# BlindsControl.net
KiCad netlist of a schematic drawn in EAGLE
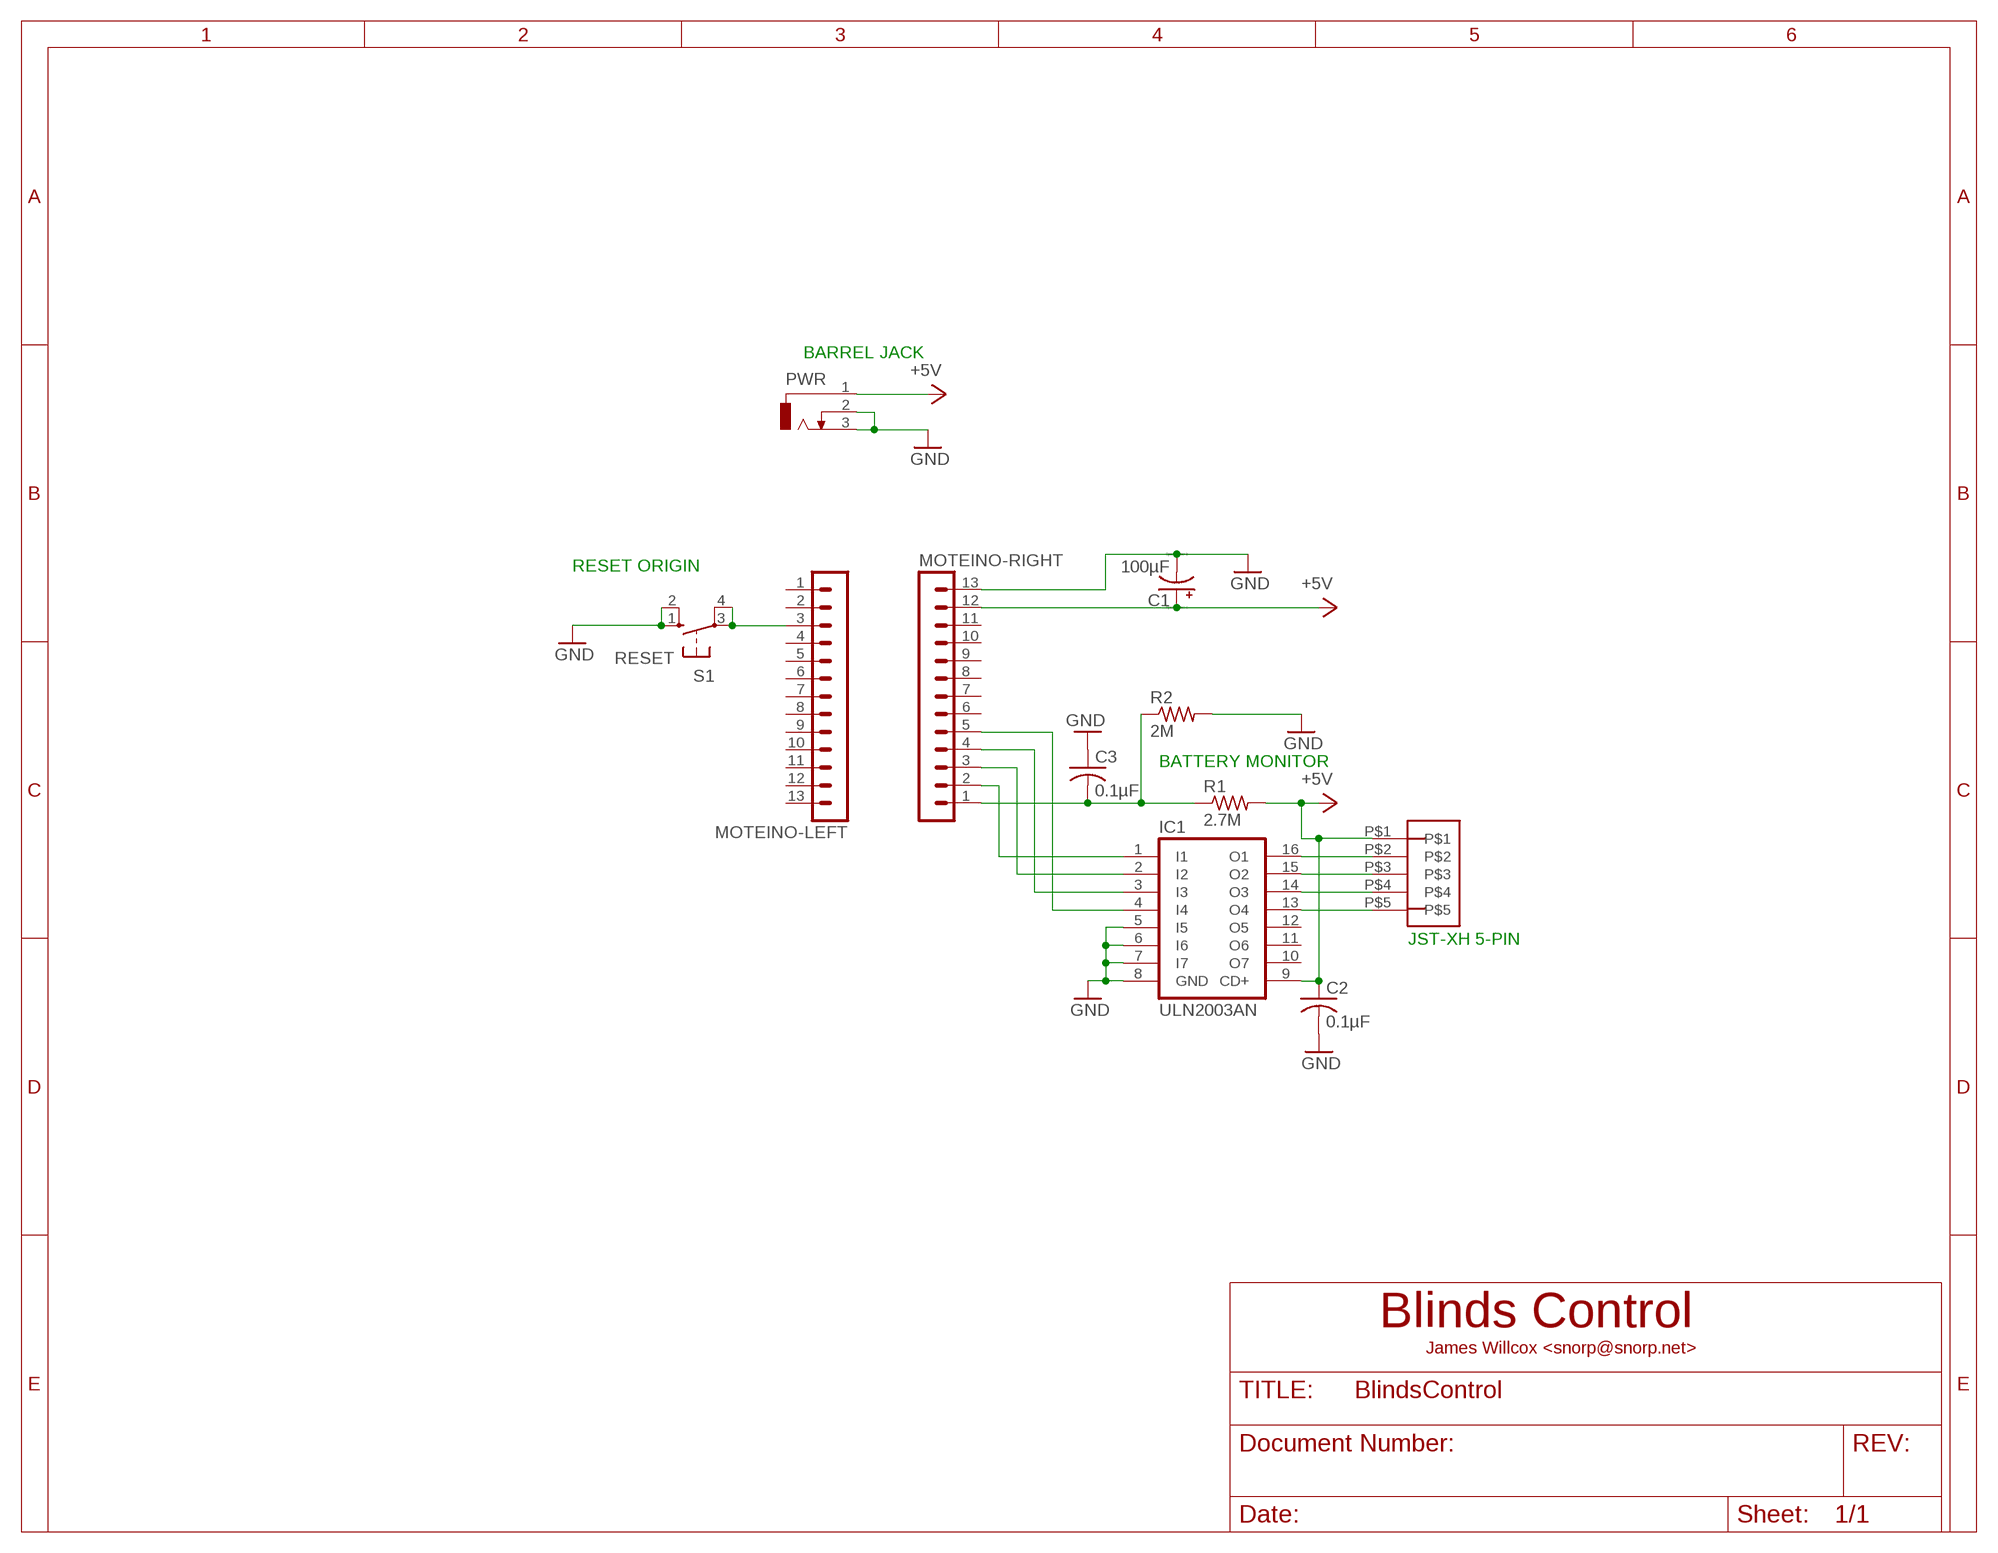
[diagram p0: schematic, sheet 1]

(export (version "E")
  (design (tool "Eeschema 10.0.6"))
  (components
    (comp (ref "C1")
      (value "100µF")
      (footprint "eagle-import:TAP5-60")
      (libsource (lib "eagle-import") (part "CPOL-USTAP5-60"))
    )
    (comp (ref "C2")
      (value "0.1µF")
      (footprint "eagle-import:C025-025X050")
      (libsource (lib "eagle-import") (part "C-US025-025X050"))
    )
    (comp (ref "C3")
      (value "0.1µF")
      (footprint "eagle-import:C025-025X050")
      (libsource (lib "eagle-import") (part "C-US025-025X050"))
    )
    (comp (ref "IC1")
      (value "ULN2003AN")
      (footprint "eagle-import:DIL16")
      (libsource (lib "eagle-import") (part "ULN2003AN"))
    )
    (comp (ref "MOTEINO-LEFT")
      (value "MA13-1")
      (footprint "eagle-import:MA13-1")
      (libsource (lib "eagle-import") (part "MA13-1"))
    )
    (comp (ref "MOTEINO-RIGHT")
      (value "MA13-1")
      (footprint "eagle-import:MA13-1")
      (libsource (lib "eagle-import") (part "MA13-1"))
    )
    (comp (ref "PWR")
      (value "DCJ0303")
      (footprint "eagle-import:DCJ0303")
      (libsource (lib "eagle-import") (part "DCJ0303"))
    )
    (comp (ref "R1")
      (value "2.7M")
      (footprint "eagle-import:0207_7")
      (libsource (lib "eagle-import") (part "R-US_0207/7"))
    )
    (comp (ref "R2")
      (value "2M")
      (footprint "eagle-import:0207_7")
      (libsource (lib "eagle-import") (part "R-US_0207/7"))
    )
    (comp (ref "S1")
      (value "RESET")
      (footprint "eagle-import:B3F-10XX")
      (fields (field (name "MPN") "B3F-1000"))
      (libsource (lib "eagle-import") (part "10-XX"))
    )
    (comp (ref "U$1")
      (value "5_PIN_JST-XH")
      (footprint "eagle-import:5_PIN_JST-XH")
      (libsource (lib "eagle-import") (part "5_PIN_JST-XH"))
    )
  )
  (nets
    (net (code "1") (name "+5V") (class "Default")
      (node (ref "C1") (pin "+") (pinfunction "+_+") (pintype "passive"))
      (node (ref "C2") (pin "1") (pinfunction "1_1") (pintype "passive"))
      (node (ref "IC1") (pin "9") (pinfunction "CD+_9") (pintype "passive"))
      (node (ref "MOTEINO-RIGHT") (pin "12") (pinfunction "12_12") (pintype "passive"))
      (node (ref "PWR") (pin "1") (pinfunction "1_1") (pintype "passive"))
      (node (ref "R1") (pin "2") (pinfunction "2_2") (pintype "passive"))
      (node (ref "U$1") (pin "P$1") (pinfunction "P$1_P$1") (pintype "bidirectional"))
    )
    (net (code "2") (name "GND") (class "Default")
      (node (ref "C1") (pin "-") (pinfunction "-_-") (pintype "passive"))
      (node (ref "C2") (pin "2") (pinfunction "2_2") (pintype "passive"))
      (node (ref "C3") (pin "1") (pinfunction "1_1") (pintype "passive"))
      (node (ref "IC1") (pin "5") (pinfunction "I5_5") (pintype "input"))
      (node (ref "IC1") (pin "6") (pinfunction "I6_6") (pintype "input"))
      (node (ref "IC1") (pin "7") (pinfunction "I7_7") (pintype "input"))
      (node (ref "IC1") (pin "8") (pinfunction "GND_8") (pintype "power_in"))
      (node (ref "MOTEINO-RIGHT") (pin "13") (pinfunction "13_13") (pintype "passive"))
      (node (ref "PWR") (pin "2") (pinfunction "2_2") (pintype "passive"))
      (node (ref "PWR") (pin "3") (pinfunction "3_3") (pintype "passive"))
      (node (ref "R2") (pin "2") (pinfunction "2_2") (pintype "passive"))
      (node (ref "S1") (pin "1") (pinfunction "S_1") (pintype "passive"))
      (node (ref "S1") (pin "2") (pinfunction "S1_2") (pintype "passive"))
    )
    (net (code "3") (name "Net-(C3-Pad2)") (class "Default")
      (node (ref "C3") (pin "2") (pinfunction "2_2") (pintype "passive"))
      (node (ref "MOTEINO-RIGHT") (pin "1") (pinfunction "1_1") (pintype "passive"))
      (node (ref "R1") (pin "1") (pinfunction "1_1") (pintype "passive"))
      (node (ref "R2") (pin "1") (pinfunction "1_1") (pintype "passive"))
    )
    (net (code "4") (name "Net-(IC1-I1)") (class "Default")
      (node (ref "IC1") (pin "1") (pinfunction "I1_1") (pintype "input"))
      (node (ref "MOTEINO-RIGHT") (pin "2") (pinfunction "2_2") (pintype "passive"))
    )
    (net (code "5") (name "Net-(IC1-I2)") (class "Default")
      (node (ref "IC1") (pin "2") (pinfunction "I2_2") (pintype "input"))
      (node (ref "MOTEINO-RIGHT") (pin "3") (pinfunction "3_3") (pintype "passive"))
    )
    (net (code "6") (name "Net-(IC1-I3)") (class "Default")
      (node (ref "IC1") (pin "3") (pinfunction "I3_3") (pintype "input"))
      (node (ref "MOTEINO-RIGHT") (pin "4") (pinfunction "4_4") (pintype "passive"))
    )
    (net (code "7") (name "Net-(IC1-I4)") (class "Default")
      (node (ref "IC1") (pin "4") (pinfunction "I4_4") (pintype "input"))
      (node (ref "MOTEINO-RIGHT") (pin "5") (pinfunction "5_5") (pintype "passive"))
    )
    (net (code "8") (name "Net-(IC1-O1)") (class "Default")
      (node (ref "IC1") (pin "16") (pinfunction "O1_16") (pintype "open_collector"))
      (node (ref "U$1") (pin "P$2") (pinfunction "P$2_P$2") (pintype "bidirectional"))
    )
    (net (code "9") (name "Net-(IC1-O2)") (class "Default")
      (node (ref "IC1") (pin "15") (pinfunction "O2_15") (pintype "open_collector"))
      (node (ref "U$1") (pin "P$3") (pinfunction "P$3_P$3") (pintype "bidirectional"))
    )
    (net (code "10") (name "Net-(IC1-O3)") (class "Default")
      (node (ref "IC1") (pin "14") (pinfunction "O3_14") (pintype "open_collector"))
      (node (ref "U$1") (pin "P$4") (pinfunction "P$4_P$4") (pintype "bidirectional"))
    )
    (net (code "11") (name "Net-(IC1-O4)") (class "Default")
      (node (ref "IC1") (pin "13") (pinfunction "O4_13") (pintype "open_collector"))
      (node (ref "U$1") (pin "P$5") (pinfunction "P$5_P$5") (pintype "bidirectional"))
    )
    (net (code "12") (name "Net-(S1-P)") (class "Default")
      (node (ref "MOTEINO-LEFT") (pin "3") (pinfunction "3_3") (pintype "passive"))
      (node (ref "S1") (pin "3") (pinfunction "P_3") (pintype "passive"))
      (node (ref "S1") (pin "4") (pinfunction "P1_4") (pintype "passive"))
    )
    (net (code "13") (name "unconnected-(IC1-O5-Pad12)") (class "Default")
      (node (ref "IC1") (pin "12") (pinfunction "O5_12") (pintype "open_collector"))
    )
    (net (code "14") (name "unconnected-(IC1-O6-Pad11)") (class "Default")
      (node (ref "IC1") (pin "11") (pinfunction "O6_11") (pintype "open_collector"))
    )
    (net (code "15") (name "unconnected-(IC1-O7-Pad10)") (class "Default")
      (node (ref "IC1") (pin "10") (pinfunction "O7_10") (pintype "open_collector"))
    )
    (net (code "16") (name "unconnected-(MOTEINO-LEFT-Pad1)") (class "Default")
      (node (ref "MOTEINO-LEFT") (pin "1") (pinfunction "1_1") (pintype "passive"))
    )
    (net (code "17") (name "unconnected-(MOTEINO-LEFT-Pad2)") (class "Default")
      (node (ref "MOTEINO-LEFT") (pin "2") (pinfunction "2_2") (pintype "passive"))
    )
    (net (code "18") (name "unconnected-(MOTEINO-LEFT-Pad4)") (class "Default")
      (node (ref "MOTEINO-LEFT") (pin "4") (pinfunction "4_4") (pintype "passive"))
    )
    (net (code "19") (name "unconnected-(MOTEINO-LEFT-Pad5)") (class "Default")
      (node (ref "MOTEINO-LEFT") (pin "5") (pinfunction "5_5") (pintype "passive"))
    )
    (net (code "20") (name "unconnected-(MOTEINO-LEFT-Pad6)") (class "Default")
      (node (ref "MOTEINO-LEFT") (pin "6") (pinfunction "6_6") (pintype "passive"))
    )
    (net (code "21") (name "unconnected-(MOTEINO-LEFT-Pad7)") (class "Default")
      (node (ref "MOTEINO-LEFT") (pin "7") (pinfunction "7_7") (pintype "passive"))
    )
    (net (code "22") (name "unconnected-(MOTEINO-LEFT-Pad8)") (class "Default")
      (node (ref "MOTEINO-LEFT") (pin "8") (pinfunction "8_8") (pintype "passive"))
    )
    (net (code "23") (name "unconnected-(MOTEINO-LEFT-Pad9)") (class "Default")
      (node (ref "MOTEINO-LEFT") (pin "9") (pinfunction "9_9") (pintype "passive"))
    )
    (net (code "24") (name "unconnected-(MOTEINO-LEFT-Pad10)") (class "Default")
      (node (ref "MOTEINO-LEFT") (pin "10") (pinfunction "10_10") (pintype "passive"))
    )
    (net (code "25") (name "unconnected-(MOTEINO-LEFT-Pad11)") (class "Default")
      (node (ref "MOTEINO-LEFT") (pin "11") (pinfunction "11_11") (pintype "passive"))
    )
    (net (code "26") (name "unconnected-(MOTEINO-LEFT-Pad12)") (class "Default")
      (node (ref "MOTEINO-LEFT") (pin "12") (pinfunction "12_12") (pintype "passive"))
    )
    (net (code "27") (name "unconnected-(MOTEINO-LEFT-Pad13)") (class "Default")
      (node (ref "MOTEINO-LEFT") (pin "13") (pinfunction "13_13") (pintype "passive"))
    )
    (net (code "28") (name "unconnected-(MOTEINO-RIGHT-Pad6)") (class "Default")
      (node (ref "MOTEINO-RIGHT") (pin "6") (pinfunction "6_6") (pintype "passive"))
    )
    (net (code "29") (name "unconnected-(MOTEINO-RIGHT-Pad7)") (class "Default")
      (node (ref "MOTEINO-RIGHT") (pin "7") (pinfunction "7_7") (pintype "passive"))
    )
    (net (code "30") (name "unconnected-(MOTEINO-RIGHT-Pad8)") (class "Default")
      (node (ref "MOTEINO-RIGHT") (pin "8") (pinfunction "8_8") (pintype "passive"))
    )
    (net (code "31") (name "unconnected-(MOTEINO-RIGHT-Pad9)") (class "Default")
      (node (ref "MOTEINO-RIGHT") (pin "9") (pinfunction "9_9") (pintype "passive"))
    )
    (net (code "32") (name "unconnected-(MOTEINO-RIGHT-Pad10)") (class "Default")
      (node (ref "MOTEINO-RIGHT") (pin "10") (pinfunction "10_10") (pintype "passive"))
    )
    (net (code "33") (name "unconnected-(MOTEINO-RIGHT-Pad11)") (class "Default")
      (node (ref "MOTEINO-RIGHT") (pin "11") (pinfunction "11_11") (pintype "passive"))
    )
  )
)
